# ray0.net
KiCad netlist of a schematic drawn in EAGLE
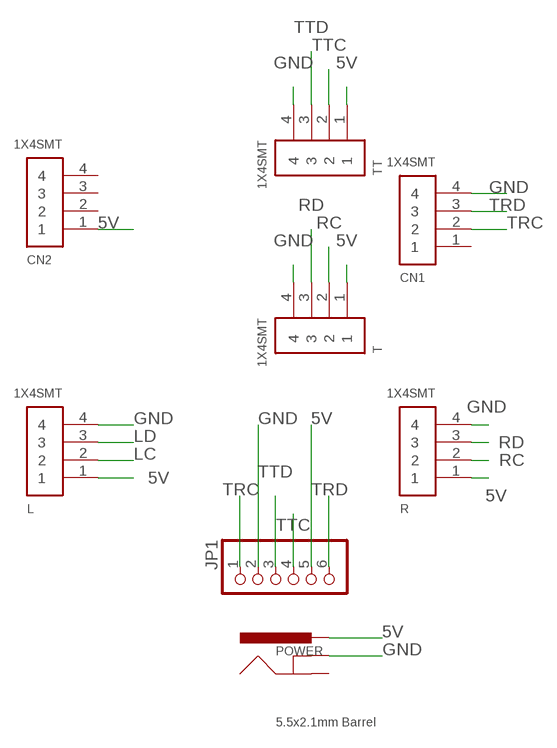
[diagram p0: schematic, sheet 1]

(export (version "E")
  (design (tool "Eeschema 10.0.6"))
  (components
    (comp (ref "CN1")
      (value "1X4SMT")
      (footprint "eagle-import:1X4-SMT")
      (libsource (lib "eagle-import") (part "1X4SMT"))
    )
    (comp (ref "CN2")
      (value "1X4SMT")
      (footprint "eagle-import:1X4-SMT")
      (libsource (lib "eagle-import") (part "1X4SMT"))
    )
    (comp (ref "JP1")
      (value "PINHD-1X6")
      (footprint "eagle-import:1X06")
      (libsource (lib "eagle-import") (part "PINHD-1X6"))
    )
    (comp (ref "L")
      (value "1X4SMT")
      (footprint "eagle-import:1X4-SMT")
      (libsource (lib "eagle-import") (part "1X4SMT"))
    )
    (comp (ref "POWER")
      (value "5.5x2.1mm Barrel")
      (footprint "eagle-import:POWER_JACK_SMD")
      (libsource (lib "eagle-import") (part "POWER_JACKSMD"))
    )
    (comp (ref "R")
      (value "1X4SMT")
      (footprint "eagle-import:1X4-SMT")
      (libsource (lib "eagle-import") (part "1X4SMT"))
    )
    (comp (ref "T")
      (value "1X4SMT")
      (footprint "eagle-import:1X4-SMT")
      (libsource (lib "eagle-import") (part "1X4SMT"))
    )
    (comp (ref "TT")
      (value "1X4SMT")
      (footprint "eagle-import:1X4-SMT")
      (libsource (lib "eagle-import") (part "1X4SMT"))
    )
  )
  (nets
    (net (code "1") (name "/5V") (class "Default")
      (node (ref "CN2") (pin "1") (pinfunction "1_1") (pintype "bidirectional"))
      (node (ref "JP1") (pin "5") (pinfunction "5_5") (pintype "passive"))
      (node (ref "L") (pin "1") (pinfunction "1_1") (pintype "bidirectional"))
      (node (ref "POWER") (pin "VIN0") (pinfunction "PWR_VIN0") (pintype "bidirectional"))
      (node (ref "POWER") (pin "VIN1") (pinfunction "PWR_VIN1") (pintype "bidirectional"))
      (node (ref "R") (pin "1") (pinfunction "1_1") (pintype "bidirectional"))
      (node (ref "T") (pin "1") (pinfunction "1_1") (pintype "bidirectional"))
      (node (ref "TT") (pin "1") (pinfunction "1_1") (pintype "bidirectional"))
    )
    (net (code "2") (name "/GND") (class "Default")
      (node (ref "CN1") (pin "4") (pinfunction "4_4") (pintype "bidirectional"))
      (node (ref "JP1") (pin "2") (pinfunction "2_2") (pintype "passive"))
      (node (ref "L") (pin "4") (pinfunction "4_4") (pintype "bidirectional"))
      (node (ref "POWER") (pin "GND") (pinfunction "GNDBREAK_GND") (pintype "bidirectional"))
      (node (ref "R") (pin "4") (pinfunction "4_4") (pintype "bidirectional"))
      (node (ref "T") (pin "4") (pinfunction "4_4") (pintype "bidirectional"))
      (node (ref "TT") (pin "4") (pinfunction "4_4") (pintype "bidirectional"))
    )
    (net (code "3") (name "/LC") (class "Default")
      (node (ref "L") (pin "2") (pinfunction "2_2") (pintype "bidirectional"))
    )
    (net (code "4") (name "/LD") (class "Default")
      (node (ref "L") (pin "3") (pinfunction "3_3") (pintype "bidirectional"))
    )
    (net (code "5") (name "/RC") (class "Default")
      (node (ref "R") (pin "2") (pinfunction "2_2") (pintype "bidirectional"))
      (node (ref "T") (pin "2") (pinfunction "2_2") (pintype "bidirectional"))
    )
    (net (code "6") (name "/RD") (class "Default")
      (node (ref "R") (pin "3") (pinfunction "3_3") (pintype "bidirectional"))
      (node (ref "T") (pin "3") (pinfunction "3_3") (pintype "bidirectional"))
    )
    (net (code "7") (name "/TRC") (class "Default")
      (node (ref "CN1") (pin "2") (pinfunction "2_2") (pintype "bidirectional"))
      (node (ref "JP1") (pin "1") (pinfunction "1_1") (pintype "passive"))
    )
    (net (code "8") (name "/TRD") (class "Default")
      (node (ref "CN1") (pin "3") (pinfunction "3_3") (pintype "bidirectional"))
      (node (ref "JP1") (pin "6") (pinfunction "6_6") (pintype "passive"))
    )
    (net (code "9") (name "/TTC") (class "Default")
      (node (ref "JP1") (pin "4") (pinfunction "4_4") (pintype "passive"))
      (node (ref "TT") (pin "2") (pinfunction "2_2") (pintype "bidirectional"))
    )
    (net (code "10") (name "/TTD") (class "Default")
      (node (ref "JP1") (pin "3") (pinfunction "3_3") (pintype "passive"))
      (node (ref "TT") (pin "3") (pinfunction "3_3") (pintype "bidirectional"))
    )
    (net (code "11") (name "unconnected-(CN1-Pad1)") (class "Default")
      (node (ref "CN1") (pin "1") (pinfunction "1_1") (pintype "bidirectional"))
    )
    (net (code "12") (name "unconnected-(CN2-Pad2)") (class "Default")
      (node (ref "CN2") (pin "2") (pinfunction "2_2") (pintype "bidirectional"))
    )
    (net (code "13") (name "unconnected-(CN2-Pad3)") (class "Default")
      (node (ref "CN2") (pin "3") (pinfunction "3_3") (pintype "bidirectional"))
    )
    (net (code "14") (name "unconnected-(CN2-Pad4)") (class "Default")
      (node (ref "CN2") (pin "4") (pinfunction "4_4") (pintype "bidirectional"))
    )
    (net (code "15") (name "unconnected-(POWER-GND-PadP$4)") (class "Default")
      (node (ref "POWER") (pin "P$4") (pinfunction "GND_P$4") (pintype "bidirectional"))
    )
  )
)
